# hand_pdn_v2.net
KiCad netlist of a schematic drawn in Altium Designer
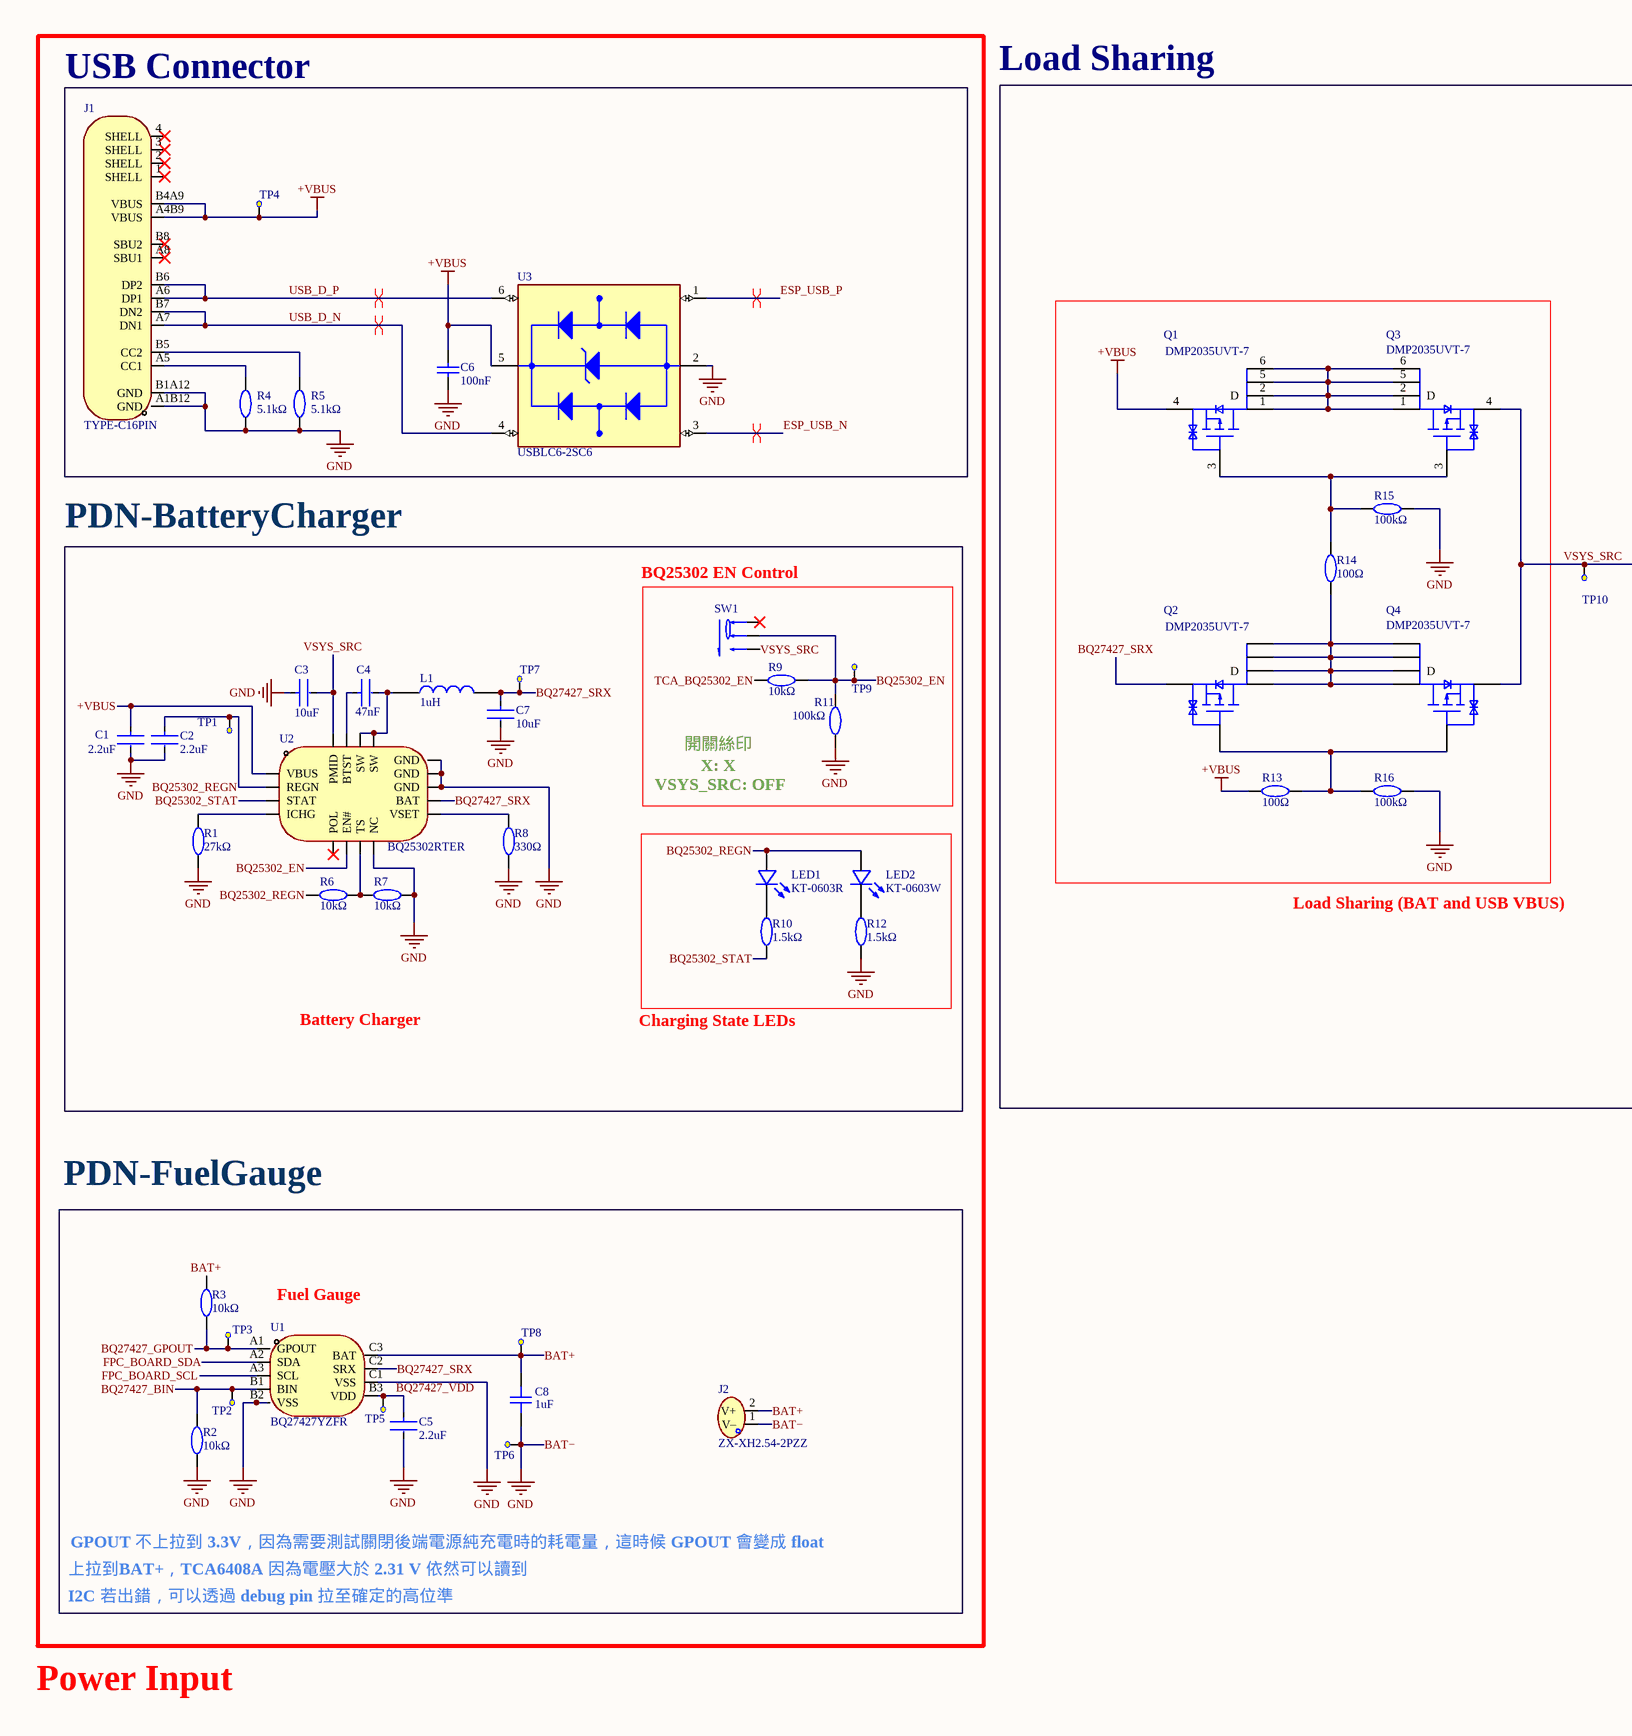
[diagram p0: hand_pdn_v2.SchDoc, left]
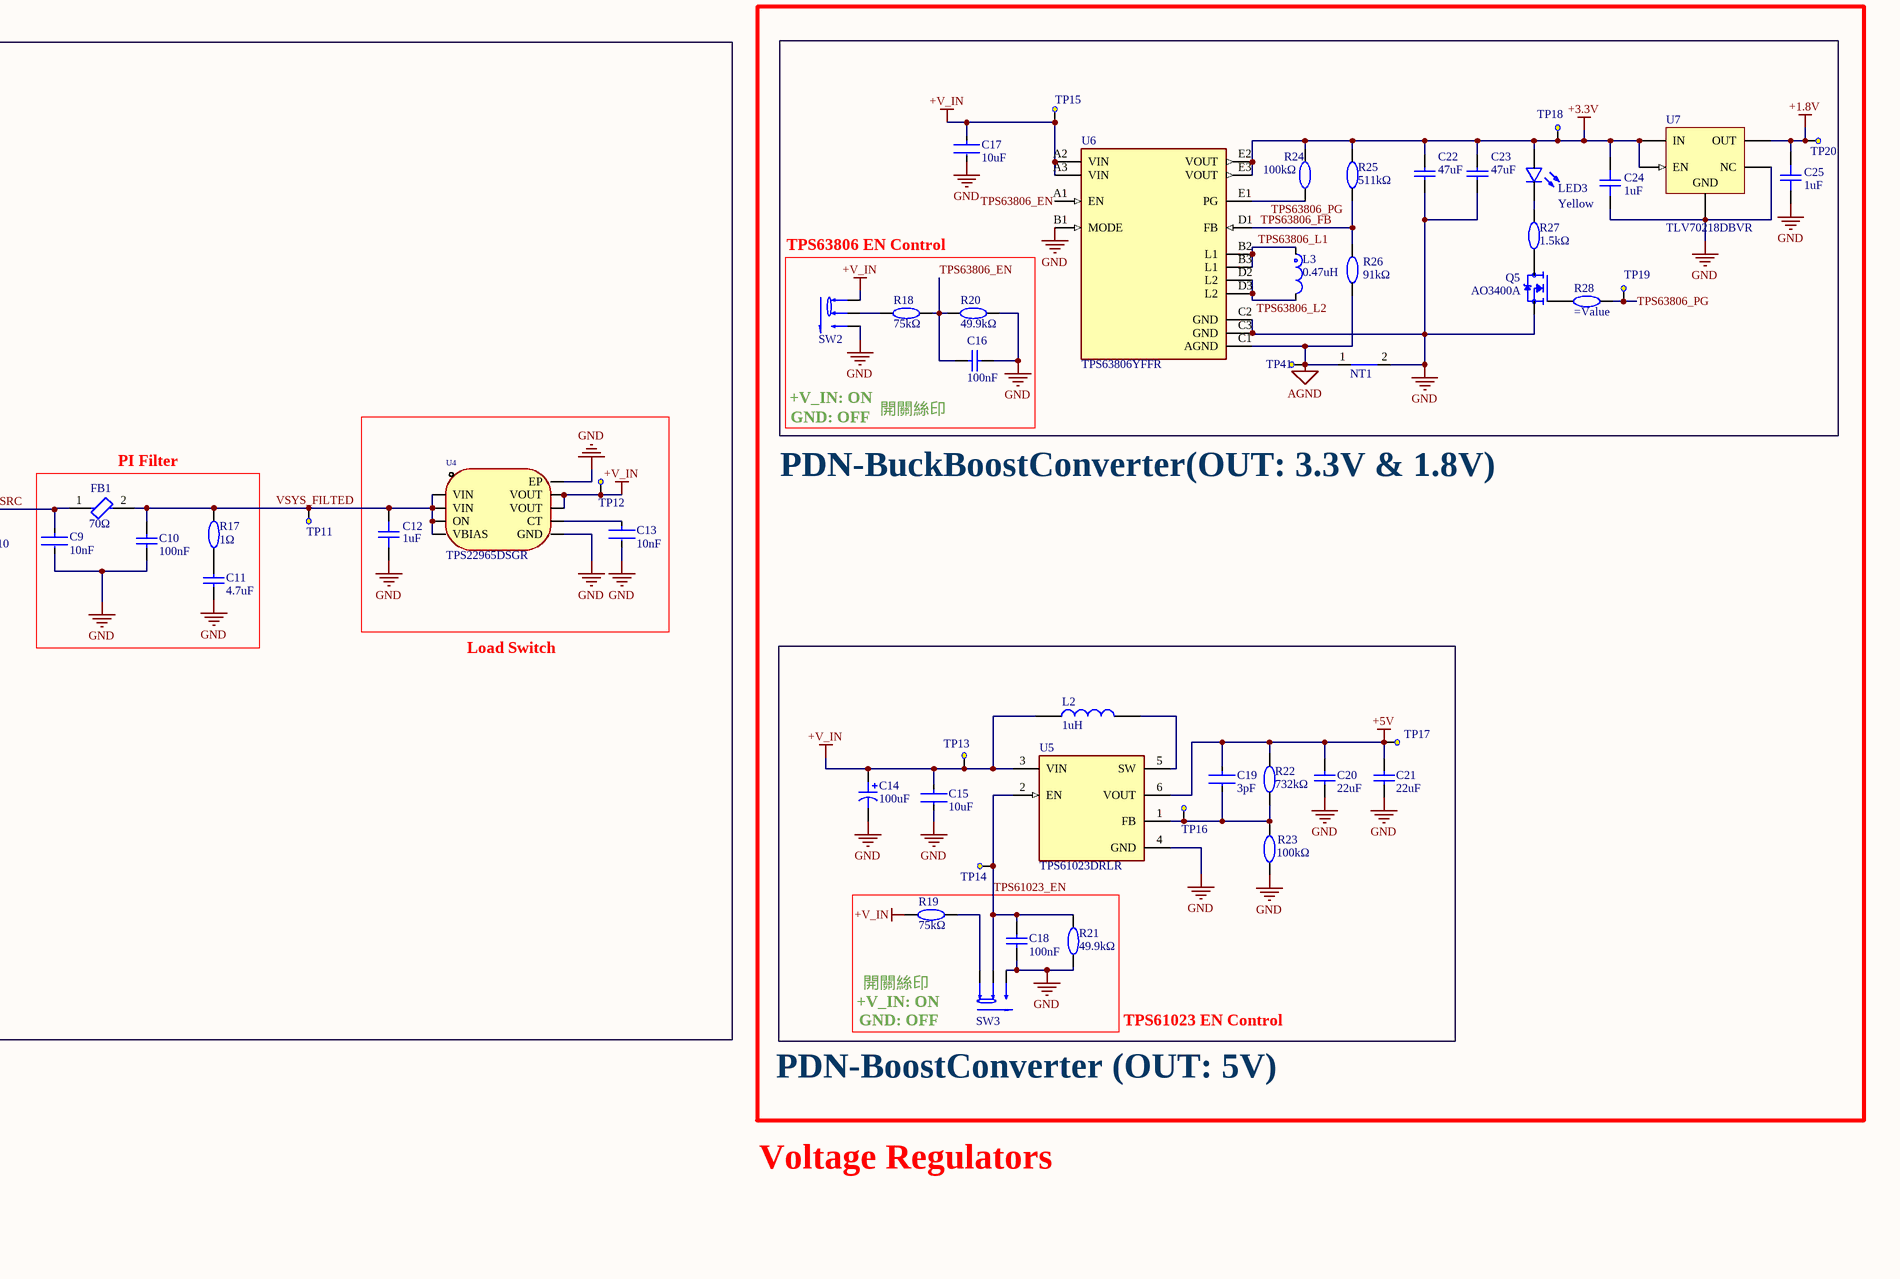
[diagram p1: hand_pdn_v2.SchDoc, right]

(export (version "E")
  (design (tool "Eeschema 10.0.6"))
  (components
    (comp (ref "C1")
      (value "2.2uF")
      (footprint "FP-CL10-IPC_A")
      (description "Cap Ceramic 2.2uF 16V X5R ±10% Pad SMD 0603 +85°C T/R")
      (fields (field (name "TOLERANCE") "10%") (field (name "VOLTAGE") "16V"))
      (libsource (lib "hand_ad_lib") (part "CL10A225KO8NNNC"))
    )
    (comp (ref "C2")
      (value "2.2uF")
      (footprint "FP-CL10-IPC_A")
      (description "Cap Ceramic 2.2uF 16V X5R ±10% Pad SMD 0603 +85°C T/R")
      (fields (field (name "TOLERANCE") "10%") (field (name "VOLTAGE") "16V"))
      (libsource (lib "hand_ad_lib") (part "CL10A225KO8NNNC"))
    )
    (comp (ref "C3")
      (value "10uF")
      (footprint "FP-CL10-IPC_A")
      (description "Cap Ceramic 10uF 25V X5R ±20% Pad SMD 0603 +85°C T/R")
      (fields (field (name "TOLERANCE") "20%"))
      (libsource (lib "hand_ad_lib") (part "CL10A106MA8NRNC"))
    )
    (comp (ref "C4")
      (value "47nF")
      (footprint "FP-CL579-IPC_A")
      (description "Cap Ceramic 47nF 16V X7R ±10% SMD 0402 +125°C Paper T/R")
      (fields (field (name "VOLTAGE") "16V") (field (name "TOLERANCE") "10%"))
      (libsource (lib "hand_ad_lib") (part "CL05B473KO5NNNC"))
    )
    (comp (ref "C5")
      (value "2.2uF")
      (footprint "FP-CL10-IPC_A")
      (description "Cap Ceramic 2.2uF 16V X5R ±10% Pad SMD 0603 +85°C T/R")
      (fields (field (name "TOLERANCE") "10%") (field (name "VOLTAGE") "16V"))
      (libsource (lib "hand_ad_lib") (part "CL10A225KO8NNNC"))
    )
    (comp (ref "C6")
      (value "100nF")
      (footprint "CAPC1050X55X23NL05T13")
      (description "Chip Capacitor, 100 nF, +/- 10%, 16 V, -55 to 125 degC, 0402 (1005 Metric), RoHS, Tape and Reel")
      (fields (field (name "MANUFACTURER") "Samsung Electro-Mechanics"))
      (libsource (lib "hand_ad_lib") (part "CL05B104KO5NNNC"))
    )
    (comp (ref "C7")
      (value "10uF")
      (footprint "FP-CL10-IPC_A")
      (description "Cap Ceramic 10uF 25V X5R ±20% Pad SMD 0603 +85°C T/R")
      (fields (field (name "TOLERANCE") "20%"))
      (libsource (lib "hand_ad_lib") (part "CL10A106MA8NRNC"))
    )
    (comp (ref "C8")
      (value "1uF")
      (footprint "C0402")
      (description "MLCC, 1 uF, 25 V, ± 10%, X5R, 0402 [1005 Metric]")
      (fields
        (field (name "MANUFACTURER") "SAMSUNG(三星)")
        (field (name "MANUFACTURER PART") "CL05A105KA5NQNC")
        (field (name "NAME") "1uF")
      )
      (libsource (lib "hand_ad_lib") (part "CL05A105KA5NQNC"))
    )
    (comp (ref "C9")
      (value "10nF")
      (footprint "FP-CL165-IPC_B")
      (description "Cap Ceramic 10nF 50V X7R ±10% SMD 0402 +125°C Paper T/R")
      (fields (field (name "VOLTAGE") "50V") (field (name "TOLERANCE") "10%"))
      (libsource (lib "hand_ad_lib") (part "CL05B103KB5NNNC"))
    )
    (comp (ref "C10")
      (value "100nF")
      (footprint "CAPC1050X55X23NL05T13")
      (description "Chip Capacitor, 100 nF, +/- 10%, 16 V, -55 to 125 degC, 0402 (1005 Metric), RoHS, Tape and Reel")
      (fields (field (name "MANUFACTURER") "Samsung Electro-Mechanics"))
      (libsource (lib "hand_ad_lib") (part "CL05B104KO5NNNC"))
    )
    (comp (ref "C11")
      (value "4.7uF")
      (footprint "C0603")
      (description "Multilayer Ceramic Capacitor, 4.7 uF, 16 V, ± 10%, X5R, 0603 [1608 Metric]")
      (fields
        (field (name "MANUFACTURER PART") "CL10A475KO8NNNC")
        (field (name "MANUFACTURER") "SAMSUNG(三星)")
        (field (name "NAME") "4.7uF")
      )
      (libsource (lib "hand_ad_lib") (part "CL10A475KO8NNNC"))
    )
    (comp (ref "C12")
      (value "1uF")
      (footprint "C0402")
      (description "MLCC, 1 uF, 25 V, ± 10%, X5R, 0402 [1005 Metric]")
      (fields
        (field (name "MANUFACTURER") "SAMSUNG(三星)")
        (field (name "MANUFACTURER PART") "CL05A105KA5NQNC")
        (field (name "NAME") "1uF")
      )
      (libsource (lib "hand_ad_lib") (part "CL05A105KA5NQNC"))
    )
    (comp (ref "C13")
      (value "10nF")
      (footprint "FP-CL165-IPC_B")
      (description "Cap Ceramic 10nF 50V X7R ±10% SMD 0402 +125°C Paper T/R")
      (fields (field (name "VOLTAGE") "50V") (field (name "TOLERANCE") "10%"))
      (libsource (lib "hand_ad_lib") (part "CL05B103KB5NNNC"))
    )
    (comp (ref "C14")
      (value "100uF")
      (footprint "CAP-SMD_BD6.3-L6.6-W6.6-LS7.2-FD")
      (description "100uF 16V SMD, D6.3xL5.4mm Aluminum Electrolytic Capacitors - SMD ROHS")
      (fields
        (field (name "MANUFACTURER") "KNSCHA(科尼盛)")
        (field (name "MANUFACTURER PART") "RVE100UF16V67RV0046")
        (field (name "NAME") "100uF")
      )
      (libsource (lib "hand_ad_lib") (part "RVE100UF16V67RV0046"))
    )
    (comp (ref "C15")
      (value "10uF")
      (footprint "FP-CL10-IPC_A")
      (description "Cap Ceramic 10uF 25V X5R ±20% Pad SMD 0603 +85°C T/R")
      (fields (field (name "TOLERANCE") "20%"))
      (libsource (lib "hand_ad_lib") (part "CL10A106MA8NRNC"))
    )
    (comp (ref "C16")
      (value "100nF")
      (footprint "CAPC1050X55X23NL05T13")
      (description "Chip Capacitor, 100 nF, +/- 10%, 16 V, -55 to 125 degC, 0402 (1005 Metric), RoHS, Tape and Reel")
      (fields (field (name "MANUFACTURER") "Samsung Electro-Mechanics"))
      (libsource (lib "hand_ad_lib") (part "CL05B104KO5NNNC"))
    )
    (comp (ref "C17")
      (value "10uF")
      (footprint "FP-CL10-IPC_A")
      (description "Cap Ceramic 10uF 25V X5R ±20% Pad SMD 0603 +85°C T/R")
      (fields (field (name "TOLERANCE") "20%"))
      (libsource (lib "hand_ad_lib") (part "CL10A106MA8NRNC"))
    )
    (comp (ref "C18")
      (value "100nF")
      (footprint "CAPC1050X55X23NL05T13")
      (description "Chip Capacitor, 100 nF, +/- 10%, 16 V, -55 to 125 degC, 0402 (1005 Metric), RoHS, Tape and Reel")
      (fields (field (name "MANUFACTURER") "Samsung Electro-Mechanics"))
      (libsource (lib "hand_ad_lib") (part "CL05B104KO5NNNC"))
    )
    (comp (ref "C19")
      (value "3pF")
      (footprint "FP-GJM155-0_05-IPC_C")
      (description "Multi-Layer Ceramic Capacitor 3pF C0G  ±0.05pF 0402 Paper T/R")
      (libsource (lib "hand_ad_lib") (part "GJM1555C1H3R0WB01D"))
    )
    (comp (ref "C20")
      (value "22uF")
      (footprint "CAPC2013X140X45ML15T25")
      (description "Multi-layer Ceramic Capacitor, 22 uF, -55 to 85 degC, 2-Pin SMD (0805), RoHS, Tape and Reel")
      (fields (field (name "MANUFACTURER") "Samsung Electro-Mechanics") (field (name "TOLERANCE") "±20%"))
      (libsource (lib "hand_ad_lib") (part "CL21A226MAQNNNE"))
    )
    (comp (ref "C21")
      (value "22uF")
      (footprint "CAPC2013X140X45ML15T25")
      (description "Multi-layer Ceramic Capacitor, 22 uF, -55 to 85 degC, 2-Pin SMD (0805), RoHS, Tape and Reel")
      (fields (field (name "MANUFACTURER") "Samsung Electro-Mechanics") (field (name "TOLERANCE") "±20%"))
      (libsource (lib "hand_ad_lib") (part "CL21A226MAQNNNE"))
    )
    (comp (ref "C22")
      (value "47uF")
      (footprint "C0805")
      (description "MLCC, 47 uF, 6.3 V, ± 20%, X5R, 0805 [2012 Metric]")
      (fields
        (field (name "MANUFACTURER PART") "CL21A476MQYNNNE")
        (field (name "MANUFACTURER") "SAMSUNG(三星)")
        (field (name "NAME") "47uF")
      )
      (libsource (lib "hand_ad_lib") (part "CL21A476MQYNNNE"))
    )
    (comp (ref "C23")
      (value "47uF")
      (footprint "C0805")
      (description "MLCC, 47 uF, 6.3 V, ± 20%, X5R, 0805 [2012 Metric]")
      (fields
        (field (name "MANUFACTURER PART") "CL21A476MQYNNNE")
        (field (name "MANUFACTURER") "SAMSUNG(三星)")
        (field (name "NAME") "47uF")
      )
      (libsource (lib "hand_ad_lib") (part "CL21A476MQYNNNE"))
    )
    (comp (ref "C24")
      (value "1uF")
      (footprint "C0402")
      (description "MLCC, 1 uF, 25 V, ± 10%, X5R, 0402 [1005 Metric]")
      (fields
        (field (name "MANUFACTURER") "SAMSUNG(三星)")
        (field (name "MANUFACTURER PART") "CL05A105KA5NQNC")
        (field (name "NAME") "1uF")
      )
      (libsource (lib "hand_ad_lib") (part "CL05A105KA5NQNC"))
    )
    (comp (ref "C25")
      (value "1uF")
      (footprint "C0402")
      (description "MLCC, 1 uF, 25 V, ± 10%, X5R, 0402 [1005 Metric]")
      (fields
        (field (name "MANUFACTURER") "SAMSUNG(三星)")
        (field (name "MANUFACTURER PART") "CL05A105KA5NQNC")
        (field (name "NAME") "1uF")
      )
      (libsource (lib "hand_ad_lib") (part "CL05A105KA5NQNC"))
    )
    (comp (ref "FB1")
      (value "70Ω")
      (footprint "FP-BLM18-0_15-t0_5-d1_2-IPC_B")
      (description "Chip Ferrite Bead, 0603, 70Ω @ 100MHz, 25%, 0.02Ω, 4A")
      (libsource (lib "hand_ad_lib") (part "BLM18SG700TZ1D"))
    )
    (comp (ref "J1")
      (value "TYPE-C16PIN")
      (footprint "USB-C-SMD_TYPE-C16PIN")
      (description "USB Type-C 16 pins connector")
      (fields (field (name "MANUFACTURER") "SHOU HAN(首韩)") (field (name "NAME") "TYPE-C16PIN"))
      (libsource (lib "hand_ad_lib") (part "TYPE-C16PIN"))
    )
    (comp (ref "J2")
      (value "ZX-XH2.54-2PZZ")
      (footprint "CONN-TH_2P-P2.50_HX25003-2A")
      (description "XH-2.54 2 Pin, through hole")
      (fields (field (name "MANUFACTURER") "Megastar(兆星)") (field (name "NAME") "ZX-XH2.54-2PZZ"))
      (libsource (lib "hand_ad_lib") (part "ZX-XH2.54-2PZZ"))
    )
    (comp (ref "L1")
      (value "1uH")
      (footprint "XEL4030101MED")
      (description "Power inductor, shielded, 20% tol, SMT, RoHS, halogen-free")
      (fields
        (field (name "MANUFACTURER_PART_NUMBER") "XEL4030-102MEC")
        (field (name "MOUSER PART NUMBER") "994-XEL4030-102MEC")
      )
      (libsource (lib "hand_ad_lib") (part "XEL4030-102MEC"))
    )
    (comp (ref "L2")
      (value "1uH")
      (footprint "XEL4030101MED")
      (description "Power inductor, shielded, 20% tol, SMT, RoHS, halogen-free")
      (fields
        (field (name "MANUFACTURER_PART_NUMBER") "XEL4030-102MEC")
        (field (name "MOUSER PART NUMBER") "994-XEL4030-102MEC")
      )
      (libsource (lib "hand_ad_lib") (part "XEL4030-102MEC"))
    )
    (comp (ref "L3")
      (value "0.47uH")
      (footprint "FP-XFL4015-MFG")
      (description "Shielded Power Fixed Inductor 0.47µH 11.2A 8.36mOhm AECQ2, SFR 89MHz")
      (fields (field (name "TOLERANCE") "20%"))
      (libsource (lib "hand_ad_lib") (part "XFL4015-471MEC"))
    )
    (comp (ref "LED1")
      (value "KT-0603R")
      (footprint "LED0603-RD")
      (description "LED, Red 0603")
      (fields (field (name "MANUFACTURER") "KENTO") (field (name "NAME") "KT-0603R"))
      (libsource (lib "hand_ad_lib") (part "KT-0603R"))
    )
    (comp (ref "LED2")
      (value "KT-0603W")
      (footprint "LED0603-R-RD_WHITE")
      (description "LED, White 0603")
      (fields (field (name "MANUFACTURER") "KENTO") (field (name "NAME") "KT-0603W"))
      (libsource (lib "hand_ad_lib") (part "KT-0603W"))
    )
    (comp (ref "LED3")
      (value "19-213/Y2C-CQ2R2L/3T(CY)")
      (footprint "LED0603-RD-YELLOW")
      (description "LED, Yellow 0603")
      (fields (field (name "MANUFACTURER") "EVERLIGHT(亿光)") (field (name "NAME") "Yellow"))
      (libsource (lib "hand_ad_lib") (part "19-213/Y2C-CQ2R2L/3T(CY)"))
    )
    (comp (ref "NT1") (value "NT") (footprint "NT") (libsource (lib "hand_ad_lib") (part "NetTie_SMD")))
    (comp (ref "Q1")
      (value "DMP2035UVT-7")
      (footprint "SOT-26_L3.0-W1.6-P0.95-LS2.8-BL")
      (description "P-Channel 20 V 35 mOhm Surface Mount Enhancement Mode Mosfet - TSOT26-6")
      (fields (field (name "MANUFACTURER") "DIODES(美台)") (field (name "NAME") "DMP2035UVT-7"))
      (libsource (lib "hand_ad_lib") (part "DMP2035UVT-7"))
    )
    (comp (ref "Q2")
      (value "DMP2035UVT-7")
      (footprint "SOT-26_L3.0-W1.6-P0.95-LS2.8-BL")
      (description "P-Channel 20 V 35 mOhm Surface Mount Enhancement Mode Mosfet - TSOT26-6")
      (fields (field (name "MANUFACTURER") "DIODES(美台)") (field (name "NAME") "DMP2035UVT-7"))
      (libsource (lib "") (part "DMP2035UVT-7_1"))
    )
    (comp (ref "Q3")
      (value "DMP2035UVT-7")
      (footprint "SOT-26_L3.0-W1.6-P0.95-LS2.8-BL")
      (description "P-Channel 20 V 35 mOhm Surface Mount Enhancement Mode Mosfet - TSOT26-6")
      (fields (field (name "MANUFACTURER") "DIODES(美台)") (field (name "NAME") "DMP2035UVT-7"))
      (libsource (lib "hand_ad_lib") (part "DMP2035UVT-7"))
    )
    (comp (ref "Q4")
      (value "DMP2035UVT-7")
      (footprint "SOT-26_L3.0-W1.6-P0.95-LS2.8-BL")
      (description "P-Channel 20 V 35 mOhm Surface Mount Enhancement Mode Mosfet - TSOT26-6")
      (fields (field (name "MANUFACTURER") "DIODES(美台)") (field (name "NAME") "DMP2035UVT-7"))
      (libsource (lib "") (part "DMP2035UVT-7_1"))
    )
    (comp (ref "Q5")
      (value "AO3400A")
      (footprint "FP-SOT23-IPC_A")
      (description "MOSFET N-CH 30V 5.7A SOT23, C20917, Vth from 0.65 - 1.45 V")
      (libsource (lib "hand_ad_lib") (part "AO3400A"))
    )
    (comp (ref "R1")
      (value "27kΩ")
      (footprint "R0603")
      (description "Resistor, Res Thick Film 0603 27K Ohm 1% 0.1W ±100ppm/°C Pad SMD T/R")
      (fields
        (field (name "MANUFACTURER") "UNI-ROYAL(厚声)")
        (field (name "MANUFACTURER PART") "0603WAF2702T5E")
        (field (name "NAME") "27kΩ")
      )
      (libsource (lib "hand_ad_lib") (part "0603WAF2702T5E"))
    )
    (comp (ref "R2")
      (value "10kΩ")
      (footprint "R0402")
      (description "Resistor, Res Thick Film 0402 10K Ohm 1% 0.063W(1/16W) ±100ppm/°C Pad SMD T/R")
      (fields
        (field (name "MANUFACTURER") "UNI-ROYAL(厚声)")
        (field (name "MANUFACTURER PART") "0402WGF1002TCE")
        (field (name "NAME") "10kΩ")
      )
      (libsource (lib "hand_ad_lib") (part "0402WGF1002TCE"))
    )
    (comp (ref "R3")
      (value "10kΩ")
      (footprint "R0402")
      (description "Resistor, Res Thick Film 0402 10K Ohm 1% 0.063W(1/16W) ±100ppm/°C Pad SMD T/R")
      (fields
        (field (name "MANUFACTURER") "UNI-ROYAL(厚声)")
        (field (name "MANUFACTURER PART") "0402WGF1002TCE")
        (field (name "NAME") "10kΩ")
      )
      (libsource (lib "hand_ad_lib") (part "0402WGF1002TCE"))
    )
    (comp (ref "R4")
      (value "5.1kΩ")
      (footprint "R0402")
      (fields
        (field (name "MANUFACTURER") "UNI-ROYAL(厚声)")
        (field (name "MANUFACTURER PART") "0402WGF5101TCE")
        (field (name "TOLERANCE") "±1%")
        (field (name "NAME") "5.1kΩ")
      )
      (libsource (lib "hand_ad_lib") (part "0402WGF5101TCE"))
    )
    (comp (ref "R5")
      (value "5.1kΩ")
      (footprint "R0402")
      (fields
        (field (name "MANUFACTURER") "UNI-ROYAL(厚声)")
        (field (name "MANUFACTURER PART") "0402WGF5101TCE")
        (field (name "TOLERANCE") "±1%")
        (field (name "NAME") "5.1kΩ")
      )
      (libsource (lib "hand_ad_lib") (part "0402WGF5101TCE"))
    )
    (comp (ref "R6")
      (value "10kΩ")
      (footprint "R0402")
      (description "Resistor, Res Thick Film 0402 10K Ohm 1% 0.063W(1/16W) ±100ppm/°C Pad SMD T/R")
      (fields
        (field (name "MANUFACTURER") "UNI-ROYAL(厚声)")
        (field (name "MANUFACTURER PART") "0402WGF1002TCE")
        (field (name "NAME") "10kΩ")
      )
      (libsource (lib "hand_ad_lib") (part "0402WGF1002TCE"))
    )
    (comp (ref "R7")
      (value "10kΩ")
      (footprint "R0402")
      (description "Resistor, Res Thick Film 0402 10K Ohm 1% 0.063W(1/16W) ±100ppm/°C Pad SMD T/R")
      (fields
        (field (name "MANUFACTURER") "UNI-ROYAL(厚声)")
        (field (name "MANUFACTURER PART") "0402WGF1002TCE")
        (field (name "NAME") "10kΩ")
      )
      (libsource (lib "hand_ad_lib") (part "0402WGF1002TCE"))
    )
    (comp (ref "R8")
      (value "330Ω")
      (footprint "R0402")
      (description "Resistor, Res Thick Film 0402 330 Ohm 1% 0.063W(1/16W) ±100ppm/°C Pad SMD T/R")
      (fields
        (field (name "MANUFACTURER") "UNI-ROYAL(厚声)")
        (field (name "MANUFACTURER PART") "0402WGF3300TCE")
        (field (name "NAME") "330Ω")
      )
      (libsource (lib "hand_ad_lib") (part "0402WGF3300TCE"))
    )
    (comp (ref "R9")
      (value "10kΩ")
      (footprint "R0402")
      (description "Resistor, Res Thick Film 0402 10K Ohm 1% 0.063W(1/16W) ±100ppm/°C Pad SMD T/R")
      (fields
        (field (name "MANUFACTURER") "UNI-ROYAL(厚声)")
        (field (name "MANUFACTURER PART") "0402WGF1002TCE")
        (field (name "NAME") "10kΩ")
      )
      (libsource (lib "hand_ad_lib") (part "0402WGF1002TCE"))
    )
    (comp (ref "R10")
      (value "1.5kΩ")
      (footprint "R0402")
      (description "Resistor, Res Thick Film 0402 1.5K Ohm 1% 0.063W(1/16W) ±100ppm/°C Pad SMD T/R")
      (fields
        (field (name "MANUFACTURER") "UNI-ROYAL(厚声)")
        (field (name "MANUFACTURER PART") "0402WGF1501TCE")
        (field (name "NAME") "1.5kΩ")
      )
      (libsource (lib "hand_ad_lib") (part "0402WGF1501TCE"))
    )
    (comp (ref "R11")
      (value "100kΩ")
      (footprint "R0402")
      (description "Resistor, Res Thick Film 0402 100K Ohm 1% 0.063W(1/16W) ±100ppm/°C Pad SMD T/R")
      (fields
        (field (name "MANUFACTURER") "UNI-ROYAL(厚声)")
        (field (name "MANUFACTURER PART") "0402WGF1003TCE")
        (field (name "NAME") "100kΩ")
      )
      (libsource (lib "hand_ad_lib") (part "0402WGF1003TCE"))
    )
    (comp (ref "R12")
      (value "1.5kΩ")
      (footprint "R0402")
      (description "Resistor, Res Thick Film 0402 1.5K Ohm 1% 0.063W(1/16W) ±100ppm/°C Pad SMD T/R")
      (fields
        (field (name "MANUFACTURER") "UNI-ROYAL(厚声)")
        (field (name "MANUFACTURER PART") "0402WGF1501TCE")
        (field (name "NAME") "1.5kΩ")
      )
      (libsource (lib "hand_ad_lib") (part "0402WGF1501TCE"))
    )
    (comp (ref "R13")
      (value "100Ω")
      (footprint "R0603")
      (description "Resistor, Res Thick Film 0603 100 Ohm 1% 0.1W(1/10W) ±200ppm/°C Pad SMD T/R")
      (fields
        (field (name "MANUFACTURER") "UNI-ROYAL(厚声)")
        (field (name "MANUFACTURER PART") "0603WAF1000T5E")
        (field (name "NAME") "100Ω")
      )
      (libsource (lib "hand_ad_lib") (part "0603WAF1000T5E"))
    )
    (comp (ref "R14")
      (value "100Ω")
      (footprint "R0603")
      (description "Resistor, Res Thick Film 0603 100 Ohm 1% 0.1W(1/10W) ±200ppm/°C Pad SMD T/R")
      (fields
        (field (name "MANUFACTURER") "UNI-ROYAL(厚声)")
        (field (name "MANUFACTURER PART") "0603WAF1000T5E")
        (field (name "NAME") "100Ω")
      )
      (libsource (lib "hand_ad_lib") (part "0603WAF1000T5E"))
    )
    (comp (ref "R15")
      (value "100kΩ")
      (footprint "R0402")
      (description "Resistor, Res Thick Film 0402 100K Ohm 1% 0.063W(1/16W) ±100ppm/°C Pad SMD T/R")
      (fields
        (field (name "MANUFACTURER") "UNI-ROYAL(厚声)")
        (field (name "MANUFACTURER PART") "0402WGF1003TCE")
        (field (name "NAME") "100kΩ")
      )
      (libsource (lib "hand_ad_lib") (part "0402WGF1003TCE"))
    )
    (comp (ref "R16")
      (value "100kΩ")
      (footprint "R0402")
      (description "Resistor, Res Thick Film 0402 100K Ohm 1% 0.063W(1/16W) ±100ppm/°C Pad SMD T/R")
      (fields
        (field (name "MANUFACTURER") "UNI-ROYAL(厚声)")
        (field (name "MANUFACTURER PART") "0402WGF1003TCE")
        (field (name "NAME") "100kΩ")
      )
      (libsource (lib "hand_ad_lib") (part "0402WGF1003TCE"))
    )
    (comp (ref "R17")
      (value "1Ω")
      (footprint "R0805")
      (fields
        (field (name "MANUFACTURER") "UNI-ROYAL(厚声)")
        (field (name "MANUFACTURER PART") "0805W8F100KT5E")
        (field (name "TOLERANCE") "±1%")
        (field (name "NAME") "1Ω")
      )
      (libsource (lib "hand_ad_lib") (part "0805W8F100KT5E"))
    )
    (comp (ref "R18")
      (value "75kΩ")
      (footprint "R0603")
      (description "Resistor, Res Thick Film 0603 75k Ohm 1% 0.1W(1/10W) ±100ppm/°C Pad SMD T/R")
      (fields
        (field (name "MANUFACTURER") "UNI-ROYAL(厚声)")
        (field (name "MANUFACTURER PART") "0603WAF7502T5E")
        (field (name "NAME") "75kΩ")
      )
      (libsource (lib "hand_ad_lib") (part "0603WAF7502T5E"))
    )
    (comp (ref "R19")
      (value "75kΩ")
      (footprint "R0603")
      (description "Resistor, Res Thick Film 0603 75k Ohm 1% 0.1W(1/10W) ±100ppm/°C Pad SMD T/R")
      (fields
        (field (name "MANUFACTURER") "UNI-ROYAL(厚声)")
        (field (name "MANUFACTURER PART") "0603WAF7502T5E")
        (field (name "NAME") "75kΩ")
      )
      (libsource (lib "hand_ad_lib") (part "0603WAF7502T5E"))
    )
    (comp (ref "R20")
      (value "49.9kΩ")
      (footprint "R0603")
      (description "Resistor, Res Thick Film 0603 49.9k Ohm 1% 0.1W(1/10W) ±100ppm/°C Pad SMD T/R")
      (fields
        (field (name "MANUFACTURER") "UNI-ROYAL(厚声)")
        (field (name "MANUFACTURER PART") "0603WAF4992T5E")
        (field (name "NAME") "49.9kΩ")
      )
      (libsource (lib "hand_ad_lib") (part "0603WAF4992T5E"))
    )
    (comp (ref "R21")
      (value "49.9kΩ")
      (footprint "R0603")
      (description "Resistor, Res Thick Film 0603 49.9k Ohm 1% 0.1W(1/10W) ±100ppm/°C Pad SMD T/R")
      (fields
        (field (name "MANUFACTURER") "UNI-ROYAL(厚声)")
        (field (name "MANUFACTURER PART") "0603WAF4992T5E")
        (field (name "NAME") "49.9kΩ")
      )
      (libsource (lib "hand_ad_lib") (part "0603WAF4992T5E"))
    )
    (comp (ref "R22")
      (value "732kΩ")
      (footprint "R0603")
      (description "RES SMD 732K OHM 1% 1/10W 0603")
      (fields
        (field (name "MANUFACTURER") "YAGEO(国巨)")
        (field (name "MANUFACTURER PART") "RC0603FR-07732KL")
        (field (name "NAME") "732kΩ")
      )
      (libsource (lib "hand_ad_lib") (part "RC0603FR-07732KL"))
    )
    (comp (ref "R23")
      (value "100kΩ")
      (footprint "R0402")
      (description "Resistor, Res Thick Film 0402 100K Ohm 1% 0.063W(1/16W) ±100ppm/°C Pad SMD T/R")
      (fields
        (field (name "MANUFACTURER") "UNI-ROYAL(厚声)")
        (field (name "MANUFACTURER PART") "0402WGF1003TCE")
        (field (name "NAME") "100kΩ")
      )
      (libsource (lib "hand_ad_lib") (part "0402WGF1003TCE"))
    )
    (comp (ref "R24")
      (value "100kΩ")
      (footprint "R0402")
      (description "Resistor, Res Thick Film 0402 100K Ohm 1% 0.063W(1/16W) ±100ppm/°C Pad SMD T/R")
      (fields
        (field (name "MANUFACTURER") "UNI-ROYAL(厚声)")
        (field (name "MANUFACTURER PART") "0402WGF1003TCE")
        (field (name "NAME") "100kΩ")
      )
      (libsource (lib "hand_ad_lib") (part "0402WGF1003TCE"))
    )
    (comp (ref "R25")
      (value "511kΩ")
      (footprint "R0603")
      (description "Resistor, Res Thick Film 0402 511k Ohm 1% 0.1W(1/10W) ±100ppm/°C Pad SMD T/R")
      (fields
        (field (name "MANUFACTURER") "YAGEO(国巨)")
        (field (name "MANUFACTURER PART") "RC0603FR-07511KL")
        (field (name "NAME") "511kΩ")
      )
      (libsource (lib "hand_ad_lib") (part "RC0603FR-07511KL"))
    )
    (comp (ref "R26")
      (value "91kΩ")
      (footprint "R0402")
      (description "SMD Chip Resistor, 91 kOhm, ± 1%, 63 mW, 0402 [1005 Metric], Thick Film, General Purpose")
      (fields
        (field (name "MANUFACTURER") "YAGEO(国巨)")
        (field (name "MANUFACTURER PART") "AC0402FR-0791KL")
        (field (name "NAME") "91kΩ")
      )
      (libsource (lib "hand_ad_lib") (part "AC0402FR-0791KL"))
    )
    (comp (ref "R27")
      (value "1.5kΩ")
      (footprint "R0402")
      (description "Resistor, Res Thick Film 0402 1.5K Ohm 1% 0.063W(1/16W) ±100ppm/°C Pad SMD T/R")
      (fields
        (field (name "MANUFACTURER") "UNI-ROYAL(厚声)")
        (field (name "MANUFACTURER PART") "0402WGF1501TCE")
        (field (name "NAME") "1.5kΩ")
      )
      (libsource (lib "hand_ad_lib") (part "0402WGF1501TCE"))
    )
    (comp (ref "R28")
      (value "~")
      (footprint "R0402")
      (description "Resistor, Res Thick Film 0402 1K Ohm 1% 0.063W(1/16W) ±100ppm/°C Pad SMD T/R")
      (fields
        (field (name "MANUFACTURER") "UNI-ROYAL(厚声)")
        (field (name "MANUFACTURER PART") "0402WGF1001TCE")
      )
      (libsource (lib "hand_ad_lib") (part "0402WGF1001TCE"))
    )
    (comp (ref "SW1")
      (value "MST-22D18G2 3J")
      (footprint "SW-SMD_SHOUHAN_MST-22D18G23J_C2875122")
      (fields (field (name "MANUFACTURER") "SHOU HAN(首韩)"))
      (libsource (lib "hand_ad_lib") (part "MST-22D18G2 3J"))
    )
    (comp (ref "SW2")
      (value "MST-22D18G2 3J")
      (footprint "SW-SMD_SHOUHAN_MST-22D18G23J_C2875122")
      (fields (field (name "MANUFACTURER") "SHOU HAN(首韩)"))
      (libsource (lib "hand_ad_lib") (part "MST-22D18G2 3J"))
    )
    (comp (ref "SW3")
      (value "MST-22D18G2 3J")
      (footprint "SW-SMD_SHOUHAN_MST-22D18G23J_C2875122")
      (fields (field (name "MANUFACTURER") "SHOU HAN(首韩)"))
      (libsource (lib "hand_ad_lib") (part "MST-22D18G2 3J"))
    )
    (comp (ref "TP1")
      (value "Test point")
      (footprint "Test_Point")
      (libsource (lib "hand_ad_lib") (part "Test_Point"))
    )
    (comp (ref "TP2")
      (value "Test point")
      (footprint "Test_Point")
      (libsource (lib "hand_ad_lib") (part "Test_Point"))
    )
    (comp (ref "TP3")
      (value "Test point")
      (footprint "Test_Point")
      (libsource (lib "hand_ad_lib") (part "Test_Point"))
    )
    (comp (ref "TP4")
      (value "Test point")
      (footprint "Test_Point")
      (libsource (lib "hand_ad_lib") (part "Test_Point"))
    )
    (comp (ref "TP5")
      (value "Test point")
      (footprint "Test_Point")
      (libsource (lib "hand_ad_lib") (part "Test_Point"))
    )
    (comp (ref "TP6")
      (value "Test point")
      (footprint "Test_Point")
      (libsource (lib "hand_ad_lib") (part "Test_Point"))
    )
    (comp (ref "TP7")
      (value "Test point")
      (footprint "Test_Point")
      (libsource (lib "hand_ad_lib") (part "Test_Point"))
    )
    (comp (ref "TP8")
      (value "Test point")
      (footprint "Test_Point")
      (libsource (lib "hand_ad_lib") (part "Test_Point"))
    )
    (comp (ref "TP9")
      (value "Test point")
      (footprint "Test_Point")
      (libsource (lib "hand_ad_lib") (part "Test_Point"))
    )
    (comp (ref "TP10")
      (value "Test point")
      (footprint "Test_Point")
      (libsource (lib "hand_ad_lib") (part "Test_Point"))
    )
    (comp (ref "TP11")
      (value "Test point")
      (footprint "Test_Point")
      (libsource (lib "hand_ad_lib") (part "Test_Point"))
    )
    (comp (ref "TP12")
      (value "Test point")
      (footprint "Test_Point")
      (libsource (lib "hand_ad_lib") (part "Test_Point"))
    )
    (comp (ref "TP13")
      (value "Test point")
      (footprint "Test_Point")
      (libsource (lib "hand_ad_lib") (part "Test_Point"))
    )
    (comp (ref "TP14")
      (value "Test point")
      (footprint "Test_Point")
      (libsource (lib "hand_ad_lib") (part "Test_Point"))
    )
    (comp (ref "TP15")
      (value "Test point")
      (footprint "Test_Point")
      (libsource (lib "hand_ad_lib") (part "Test_Point"))
    )
    (comp (ref "TP16")
      (value "Test point")
      (footprint "Test_Point")
      (libsource (lib "hand_ad_lib") (part "Test_Point"))
    )
    (comp (ref "TP17")
      (value "Test point")
      (footprint "Test_Point")
      (libsource (lib "hand_ad_lib") (part "Test_Point"))
    )
    (comp (ref "TP18")
      (value "Test point")
      (footprint "Test_Point")
      (libsource (lib "hand_ad_lib") (part "Test_Point"))
    )
    (comp (ref "TP19")
      (value "Test point")
      (footprint "Test_Point")
      (libsource (lib "hand_ad_lib") (part "Test_Point"))
    )
    (comp (ref "TP20")
      (value "Test point")
      (footprint "Test_Point")
      (libsource (lib "hand_ad_lib") (part "Test_Point"))
    )
    (comp (ref "TP41")
      (value "Test point")
      (footprint "Test_Point")
      (libsource (lib "hand_ad_lib") (part "Test_Point"))
    )
    (comp (ref "U1")
      (value "BQ27427YZFR")
      (footprint "DSBGA-9_L1.6-W1.6-R3-C3-P0.50-TL")
      (fields (field (name "MANUFACTURER") "TI(德州仪器)") (field (name "NAME") "BQ27427YZFR"))
      (libsource (lib "hand_ad_lib") (part "BQ27427YZFR"))
    )
    (comp (ref "U2")
      (value "BQ25302RTER")
      (footprint "WQFN-16_L3.0-W3.0-P0.50-BL-EP1.7")
      (description "Standalone single cell 2.0-A buck battery charger 16-WQFN -40 to 85")
      (fields (field (name "MANUFACTURER") "TI(德州仪器)") (field (name "NAME") "BQ25302RTER"))
      (libsource (lib "hand_ad_lib") (part "BQ25302RTER"))
    )
    (comp (ref "U3")
      (value "USBLC6-2SC6")
      (footprint "SOT95P280X145-6N")
      (description "17V Clamp 5A (8/20Âµs) Ipp Tvs Diode Surface Mount SOT-23-6")
      (fields (field (name "MF") "STMicroelectronics"))
      (libsource (lib "hand_ad_lib") (part "USBLC6-2SC6"))
    )
    (comp (ref "U4")
      (value "TPS22965DSGR")
      (footprint "UDFN-8_L2.0-W2.0-P0.50-TL-EP")
      (description "Tape & Reel (TR) TPS22965 e4 On/Off power distribution switch 2mm 2.5V 2.2ms 6A")
      (fields (field (name "MANUFACTURER") "TI(德州仪器)") (field (name "NAME") "TPS22965DSGR"))
      (libsource (lib "hand_ad_lib") (part "TPS22965DSGR"))
    )
    (comp (ref "U5")
      (value "TPS61023DRLR")
      (footprint "FP-DRL0006A-MFG")
      (description "3.7-A boost converter with 0.5-V ultra-low input voltage 6-SOT-5X3 -40 to 125")
      (libsource (lib "hand_ad_lib") (part "TPS61023DRLR"))
    )
    (comp (ref "U6")
      (value "TPS63806YFFR")
      (footprint "FP-YFF0015-MFG")
      (description "Low IQ Buck-Boost Converter with Small Solution Size 2A 1.3V to 5.5V 15-Pin DSBGA")
      (libsource (lib "hand_ad_lib") (part "TPS63806YFFR"))
    )
    (comp (ref "U7")
      (value "TLV70218DBVR")
      (footprint "DBV0005A_M")
      (description "300-mA, high-PSRR, low-IQ, low-dropout voltage regulator with enable 5-SOT-23 -40 to 125")
      (libsource (lib "hand_ad_lib") (part "TLV70218DBVR"))
    )
  )
  (nets
    (net (code "1") (name "+1.8V") (class "Default")
      (node (ref "C25") (pin "2") (pinfunction "2_2") (pintype "passive"))
      (node (ref "TP20") (pin "TP?") (pinfunction "Test_point_TP?") (pintype "passive"))
      (node (ref "U7") (pin "5") (pinfunction "OUT_5") (pintype "power_in"))
    )
    (net (code "2") (name "+3.3V") (class "Default")
      (node (ref "C22") (pin "2") (pinfunction "2_2") (pintype "passive"))
      (node (ref "C23") (pin "2") (pinfunction "2_2") (pintype "passive"))
      (node (ref "C24") (pin "2") (pinfunction "2_2") (pintype "passive"))
      (node (ref "LED3") (pin "2") (pinfunction "A_2") (pintype "passive"))
      (node (ref "R24") (pin "2") (pinfunction "2_2") (pintype "passive"))
      (node (ref "R25") (pin "2") (pinfunction "2_2") (pintype "passive"))
      (node (ref "TP18") (pin "TP?") (pinfunction "Test_point_TP?") (pintype "passive"))
      (node (ref "U6") (pin "E2") (pinfunction "VOUT_E2") (pintype "output"))
      (node (ref "U6") (pin "E3") (pinfunction "VOUT_E3") (pintype "output"))
      (node (ref "U7") (pin "1") (pinfunction "IN_1") (pintype "power_in"))
      (node (ref "U7") (pin "3") (pinfunction "EN_3") (pintype "input"))
    )
    (net (code "3") (name "+5V") (class "Default")
      (node (ref "C19") (pin "1") (pinfunction "1_1") (pintype "passive"))
      (node (ref "C20") (pin "2") (pinfunction "2_2") (pintype "passive"))
      (node (ref "C21") (pin "2") (pinfunction "2_2") (pintype "passive"))
      (node (ref "R22") (pin "2") (pinfunction "2_2") (pintype "passive"))
      (node (ref "TP17") (pin "TP?") (pinfunction "Test_point_TP?") (pintype "passive"))
      (node (ref "U5") (pin "6") (pinfunction "VOUT_6") (pintype "power_in"))
    )
    (net (code "4") (name "+VBUS") (class "Default")
      (node (ref "C1") (pin "1") (pinfunction "1_1") (pintype "passive"))
      (node (ref "C6") (pin "2") (pinfunction "2_2") (pintype "passive"))
      (node (ref "J1") (pin "A4B9") (pinfunction "VBUS_A4B9") (pintype "passive"))
      (node (ref "J1") (pin "B4A9") (pinfunction "VBUS_B4A9") (pintype "passive"))
      (node (ref "Q1") (pin "4") (pinfunction "S_4") (pintype "passive"))
      (node (ref "R13") (pin "2") (pinfunction "2_2") (pintype "passive"))
      (node (ref "TP4") (pin "TP?") (pinfunction "Test_point_TP?") (pintype "passive"))
      (node (ref "U2") (pin "1") (pinfunction "VBUS_1") (pintype "passive"))
      (node (ref "U3") (pin "5") (pinfunction "VBUS_5") (pintype "power_in"))
    )
    (net (code "5") (name "+V_IN") (class "Default")
      (node (ref "C14") (pin "1") (pinfunction "1_1") (pintype "passive"))
      (node (ref "C15") (pin "1") (pinfunction "1_1") (pintype "passive"))
      (node (ref "C17") (pin "1") (pinfunction "1_1") (pintype "passive"))
      (node (ref "L2") (pin "1") (pinfunction "1_1") (pintype "passive"))
      (node (ref "R19") (pin "1") (pinfunction "1_1") (pintype "passive"))
      (node (ref "SW2") (pin "1") (pinfunction "1_1") (pintype "passive"))
      (node (ref "TP12") (pin "TP?") (pinfunction "Test_point_TP?") (pintype "passive"))
      (node (ref "TP13") (pin "TP?") (pinfunction "Test_point_TP?") (pintype "passive"))
      (node (ref "TP15") (pin "TP?") (pinfunction "Test_point_TP?") (pintype "passive"))
      (node (ref "U4") (pin "7") (pinfunction "VOUT_7") (pintype "passive"))
      (node (ref "U4") (pin "8") (pinfunction "VOUT_8") (pintype "passive"))
      (node (ref "U5") (pin "3") (pinfunction "VIN_3") (pintype "power_in"))
      (node (ref "U6") (pin "A2") (pinfunction "VIN_A2") (pintype "power_in"))
      (node (ref "U6") (pin "A3") (pinfunction "VIN_A3") (pintype "power_in"))
    )
    (net (code "6") (name "/BAT+") (class "Default")
      (node (ref "C8") (pin "2") (pinfunction "2_2") (pintype "passive"))
      (node (ref "J2") (pin "2") (pinfunction "V+_2") (pintype "passive"))
      (node (ref "R3") (pin "2") (pinfunction "2_2") (pintype "passive"))
      (node (ref "TP8") (pin "TP?") (pinfunction "Test_point_TP?") (pintype "passive"))
      (node (ref "U1") (pin "C3") (pinfunction "BAT_C3") (pintype "passive"))
    )
    (net (code "7") (name "/BQ25302_EN") (class "Default")
      (node (ref "R11") (pin "2") (pinfunction "2_2") (pintype "passive"))
      (node (ref "R9") (pin "1") (pinfunction "1_1") (pintype "passive"))
      (node (ref "SW1") (pin "2") (pinfunction "2_2") (pintype "passive"))
      (node (ref "TP9") (pin "TP?") (pinfunction "Test_point_TP?") (pintype "passive"))
      (node (ref "U2") (pin "6") (pinfunction "EN#_6") (pintype "passive"))
    )
    (net (code "8") (name "/BQ25302_REGN") (class "Default")
      (node (ref "C2") (pin "1") (pinfunction "1_1") (pintype "passive"))
      (node (ref "LED1") (pin "2") (pinfunction "A_2") (pintype "passive"))
      (node (ref "LED2") (pin "1") (pinfunction "A_1") (pintype "passive"))
      (node (ref "R6") (pin "1") (pinfunction "1_1") (pintype "passive"))
      (node (ref "TP1") (pin "TP?") (pinfunction "Test_point_TP?") (pintype "passive"))
      (node (ref "U2") (pin "2") (pinfunction "REGN_2") (pintype "passive"))
    )
    (net (code "9") (name "/BQ25302_STAT") (class "Default")
      (node (ref "R10") (pin "1") (pinfunction "1_1") (pintype "passive"))
      (node (ref "U2") (pin "3") (pinfunction "STAT_3") (pintype "passive"))
    )
    (net (code "10") (name "/BQ27427_BIN") (class "Default")
      (node (ref "R2") (pin "2") (pinfunction "2_2") (pintype "passive"))
      (node (ref "TP2") (pin "TP?") (pinfunction "Test_point_TP?") (pintype "passive"))
      (node (ref "U1") (pin "B1") (pinfunction "BIN_B1") (pintype "passive"))
    )
    (net (code "11") (name "/BQ27427_GPOUT") (class "Default")
      (node (ref "R3") (pin "1") (pinfunction "1_1") (pintype "passive"))
      (node (ref "TP3") (pin "TP?") (pinfunction "Test_point_TP?") (pintype "passive"))
      (node (ref "U1") (pin "A1") (pinfunction "GPOUT_A1") (pintype "passive"))
    )
    (net (code "12") (name "/BQ27427_SRX") (class "Default")
      (node (ref "C7") (pin "1") (pinfunction "1_1") (pintype "passive"))
      (node (ref "L1") (pin "2") (pinfunction "2_2") (pintype "passive"))
      (node (ref "Q2") (pin "4") (pinfunction "S_4") (pintype "passive"))
      (node (ref "TP7") (pin "TP?") (pinfunction "Test_point_TP?") (pintype "passive"))
      (node (ref "U1") (pin "C2") (pinfunction "SRX_C2") (pintype "passive"))
      (node (ref "U2") (pin "10") (pinfunction "BAT_10") (pintype "passive"))
    )
    (net (code "13") (name "/BQ27427_VDD") (class "Default")
      (node (ref "C5") (pin "1") (pinfunction "1_1") (pintype "passive"))
      (node (ref "TP5") (pin "TP?") (pinfunction "Test_point_TP?") (pintype "passive"))
      (node (ref "U1") (pin "B3") (pinfunction "VDD_B3") (pintype "passive"))
    )
    (net (code "14") (name "/ESP_USB_N") (class "Default")
      (node (ref "U3") (pin "3") (pinfunction "I/O2_IN_3") (pintype "bidirectional"))
    )
    (net (code "15") (name "/ESP_USB_P") (class "Default")
      (node (ref "U3") (pin "1") (pinfunction "I/O1_IN_1") (pintype "bidirectional"))
    )
    (net (code "16") (name "/FPC_BOARD_SCL") (class "Default")
      (node (ref "U1") (pin "A3") (pinfunction "SCL_A3") (pintype "passive"))
    )
    (net (code "17") (name "/FPC_BOARD_SDA") (class "Default")
      (node (ref "U1") (pin "A2") (pinfunction "SDA_A2") (pintype "passive"))
    )
    (net (code "18") (name "/TCA_BQ25302_EN") (class "Default")
      (node (ref "R9") (pin "2") (pinfunction "2_2") (pintype "passive"))
    )
    (net (code "19") (name "/TPS61023_EN") (class "Default")
      (node (ref "C18") (pin "1") (pinfunction "1_1") (pintype "passive"))
      (node (ref "R21") (pin "2") (pinfunction "2_2") (pintype "passive"))
      (node (ref "SW3") (pin "2") (pinfunction "2_2") (pintype "passive"))
      (node (ref "TP14") (pin "TP?") (pinfunction "Test_point_TP?") (pintype "passive"))
      (node (ref "U5") (pin "2") (pinfunction "EN_2") (pintype "input"))
    )
    (net (code "20") (name "/TPS63806_EN") (class "Default")
      (node (ref "C16") (pin "2") (pinfunction "2_2") (pintype "passive"))
      (node (ref "R18") (pin "2") (pinfunction "2_2") (pintype "passive"))
      (node (ref "R20") (pin "1") (pinfunction "1_1") (pintype "passive"))
      (node (ref "U6") (pin "A1") (pinfunction "EN_A1") (pintype "input"))
    )
    (net (code "21") (name "/TPS63806_FB") (class "Default")
      (node (ref "R25") (pin "1") (pinfunction "1_1") (pintype "passive"))
      (node (ref "R26") (pin "2") (pinfunction "2_2") (pintype "passive"))
      (node (ref "U6") (pin "D1") (pinfunction "FB_D1") (pintype "input"))
    )
    (net (code "22") (name "/TPS63806_L1") (class "Default")
      (node (ref "L3") (pin "1") (pinfunction "1_1") (pintype "passive"))
      (node (ref "U6") (pin "B2") (pinfunction "L1_B2") (pintype "passive"))
      (node (ref "U6") (pin "B3") (pinfunction "L1_B3") (pintype "passive"))
    )
    (net (code "23") (name "/TPS63806_L2") (class "Default")
      (node (ref "L3") (pin "2") (pinfunction "2_2") (pintype "passive"))
      (node (ref "U6") (pin "D2") (pinfunction "L2_D2") (pintype "passive"))
      (node (ref "U6") (pin "D3") (pinfunction "L2_D3") (pintype "passive"))
    )
    (net (code "24") (name "/TPS63806_PG") (class "Default")
      (node (ref "R24") (pin "1") (pinfunction "1_1") (pintype "passive"))
      (node (ref "R28") (pin "2") (pinfunction "2_2") (pintype "passive"))
      (node (ref "TP19") (pin "TP?") (pinfunction "Test_point_TP?") (pintype "passive"))
      (node (ref "U6") (pin "E1") (pinfunction "PG_E1") (pintype "open_collector"))
    )
    (net (code "25") (name "/USB_D_N") (class "Default")
      (node (ref "J1") (pin "A7") (pinfunction "DN1_A7") (pintype "bidirectional"))
      (node (ref "J1") (pin "B7") (pinfunction "DN2_B7") (pintype "bidirectional"))
      (node (ref "U3") (pin "4") (pinfunction "I/O2_OUT_4") (pintype "bidirectional"))
    )
    (net (code "26") (name "/USB_D_P") (class "Default")
      (node (ref "J1") (pin "A6") (pinfunction "DP1_A6") (pintype "bidirectional"))
      (node (ref "J1") (pin "B6") (pinfunction "DP2_B6") (pintype "bidirectional"))
      (node (ref "U3") (pin "6") (pinfunction "I/O1_OUT_6") (pintype "bidirectional"))
    )
    (net (code "27") (name "/VSYS_FILTED") (class "Default")
      (node (ref "C10") (pin "2") (pinfunction "2_2") (pintype "passive"))
      (node (ref "C12") (pin "2") (pinfunction "2_2") (pintype "passive"))
      (node (ref "FB1") (pin "2") (pinfunction "2_2") (pintype "passive"))
      (node (ref "R17") (pin "2") (pinfunction "2_2") (pintype "passive"))
      (node (ref "TP11") (pin "TP?") (pinfunction "Test_point_TP?") (pintype "passive"))
      (node (ref "U4") (pin "1") (pinfunction "VIN_1") (pintype "passive"))
      (node (ref "U4") (pin "2") (pinfunction "VIN_2") (pintype "passive"))
      (node (ref "U4") (pin "3") (pinfunction "ON_3") (pintype "passive"))
      (node (ref "U4") (pin "4") (pinfunction "VBIAS_4") (pintype "passive"))
    )
    (net (code "28") (name "/VSYS_SRC") (class "Default")
      (node (ref "C3") (pin "2") (pinfunction "2_2") (pintype "passive"))
      (node (ref "C9") (pin "1") (pinfunction "1_1") (pintype "passive"))
      (node (ref "FB1") (pin "1") (pinfunction "1_1") (pintype "passive"))
      (node (ref "Q3") (pin "4") (pinfunction "S_4") (pintype "passive"))
      (node (ref "Q4") (pin "4") (pinfunction "S_4") (pintype "passive"))
      (node (ref "SW1") (pin "3") (pinfunction "3_3") (pintype "passive"))
      (node (ref "TP10") (pin "TP?") (pinfunction "Test_point_TP?") (pintype "passive"))
      (node (ref "U2") (pin "16") (pinfunction "PMID_16") (pintype "passive"))
    )
    (net (code "29") (name "AGND") (class "Default")
      (node (ref "NT1") (pin "1") (pinfunction "1_1") (pintype "passive"))
      (node (ref "R26") (pin "1") (pinfunction "1_1") (pintype "passive"))
      (node (ref "TP41") (pin "TP?") (pinfunction "Test_point_TP?") (pintype "passive"))
      (node (ref "U6") (pin "C1") (pinfunction "AGND_C1") (pintype "power_in"))
    )
    (net (code "30") (name "GND") (class "Default")
      (node (ref "C1") (pin "2") (pinfunction "2_2") (pintype "passive"))
      (node (ref "C10") (pin "1") (pinfunction "1_1") (pintype "passive"))
      (node (ref "C11") (pin "1") (pinfunction "1_1") (pintype "passive"))
      (node (ref "C12") (pin "1") (pinfunction "1_1") (pintype "passive"))
      (node (ref "C13") (pin "2") (pinfunction "2_2") (pintype "passive"))
      (node (ref "C14") (pin "2") (pinfunction "2_2") (pintype "passive"))
      (node (ref "C15") (pin "2") (pinfunction "2_2") (pintype "passive"))
      (node (ref "C16") (pin "1") (pinfunction "1_1") (pintype "passive"))
      (node (ref "C17") (pin "2") (pinfunction "2_2") (pintype "passive"))
      (node (ref "C18") (pin "2") (pinfunction "2_2") (pintype "passive"))
      (node (ref "C2") (pin "2") (pinfunction "2_2") (pintype "passive"))
      (node (ref "C20") (pin "1") (pinfunction "1_1") (pintype "passive"))
      (node (ref "C21") (pin "1") (pinfunction "1_1") (pintype "passive"))
      (node (ref "C22") (pin "1") (pinfunction "1_1") (pintype "passive"))
      (node (ref "C23") (pin "1") (pinfunction "1_1") (pintype "passive"))
      (node (ref "C24") (pin "1") (pinfunction "1_1") (pintype "passive"))
      (node (ref "C25") (pin "1") (pinfunction "1_1") (pintype "passive"))
      (node (ref "C3") (pin "1") (pinfunction "1_1") (pintype "passive"))
      (node (ref "C5") (pin "2") (pinfunction "2_2") (pintype "passive"))
      (node (ref "C6") (pin "1") (pinfunction "1_1") (pintype "passive"))
      (node (ref "C7") (pin "2") (pinfunction "2_2") (pintype "passive"))
      (node (ref "C8") (pin "1") (pinfunction "1_1") (pintype "passive"))
      (node (ref "C9") (pin "2") (pinfunction "2_2") (pintype "passive"))
      (node (ref "J1") (pin "A1B12") (pinfunction "GND_A1B12") (pintype "power_in"))
      (node (ref "J1") (pin "B1A12") (pinfunction "GND_B1A12") (pintype "power_in"))
      (node (ref "J2") (pin "1") (pinfunction "V–_1") (pintype "passive"))
      (node (ref "NT1") (pin "2") (pinfunction "2_2") (pintype "passive"))
      (node (ref "Q5") (pin "2") (pinfunction "S_2") (pintype "passive"))
      (node (ref "R1") (pin "1") (pinfunction "1_1") (pintype "passive"))
      (node (ref "R11") (pin "1") (pinfunction "1_1") (pintype "passive"))
      (node (ref "R12") (pin "1") (pinfunction "1_1") (pintype "passive"))
      (node (ref "R15") (pin "1") (pinfunction "1_1") (pintype "passive"))
      (node (ref "R16") (pin "1") (pinfunction "1_1") (pintype "passive"))
      (node (ref "R2") (pin "1") (pinfunction "1_1") (pintype "passive"))
      (node (ref "R20") (pin "2") (pinfunction "2_2") (pintype "passive"))
      (node (ref "R21") (pin "1") (pinfunction "1_1") (pintype "passive"))
      (node (ref "R23") (pin "1") (pinfunction "1_1") (pintype "passive"))
      (node (ref "R4") (pin "1") (pinfunction "1_1") (pintype "passive"))
      (node (ref "R5") (pin "1") (pinfunction "1_1") (pintype "passive"))
      (node (ref "R7") (pin "2") (pinfunction "2_2") (pintype "passive"))
      (node (ref "R8") (pin "1") (pinfunction "1_1") (pintype "passive"))
      (node (ref "SW2") (pin "3") (pinfunction "3_3") (pintype "passive"))
      (node (ref "SW3") (pin "3") (pinfunction "3_3") (pintype "passive"))
      (node (ref "TP6") (pin "TP?") (pinfunction "Test_point_TP?") (pintype "passive"))
      (node (ref "U1") (pin "B2") (pinfunction "VSS_B2") (pintype "passive"))
      (node (ref "U1") (pin "C1") (pinfunction "VSS_C1") (pintype "passive"))
      (node (ref "U2") (pin "11") (pinfunction "GND_11") (pintype "passive"))
      (node (ref "U2") (pin "12") (pinfunction "GND_12") (pintype "passive"))
      (node (ref "U2") (pin "17") (pinfunction "GND_17") (pintype "passive"))
      (node (ref "U2") (pin "8") (pinfunction "NC_8") (pintype "passive"))
      (node (ref "U3") (pin "2") (pinfunction "GND_2") (pintype "power_in"))
      (node (ref "U4") (pin "5") (pinfunction "GND_5") (pintype "passive"))
      (node (ref "U4") (pin "9") (pinfunction "EP_9") (pintype "passive"))
      (node (ref "U5") (pin "4") (pinfunction "GND_4") (pintype "power_in"))
      (node (ref "U6") (pin "B1") (pinfunction "MODE_B1") (pintype "input"))
      (node (ref "U6") (pin "C2") (pinfunction "GND_C2") (pintype "power_in"))
      (node (ref "U6") (pin "C3") (pinfunction "GND_C3") (pintype "power_in"))
      (node (ref "U7") (pin "2") (pinfunction "GND_2") (pintype "power_in"))
      (node (ref "U7") (pin "4") (pinfunction "NC_4") (pintype "passive"))
    )
    (net (code "31") (name "Net-(C4-Pad2)") (class "Default")
      (node (ref "C4") (pin "2") (pinfunction "2_2") (pintype "passive"))
      (node (ref "L1") (pin "1") (pinfunction "1_1") (pintype "passive"))
      (node (ref "U2") (pin "13") (pinfunction "SW_13") (pintype "passive"))
      (node (ref "U2") (pin "14") (pinfunction "SW_14") (pintype "passive"))
    )
    (net (code "32") (name "Net-(C11-Pad2)") (class "Default")
      (node (ref "C11") (pin "2") (pinfunction "2_2") (pintype "passive"))
      (node (ref "R17") (pin "1") (pinfunction "1_1") (pintype "passive"))
    )
    (net (code "33") (name "Net-(J1-CC1)") (class "Default")
      (node (ref "J1") (pin "A5") (pinfunction "CC1_A5") (pintype "passive"))
      (node (ref "R4") (pin "2") (pinfunction "2_2") (pintype "passive"))
    )
    (net (code "34") (name "Net-(J1-CC2)") (class "Default")
      (node (ref "J1") (pin "B5") (pinfunction "CC2_B5") (pintype "passive"))
      (node (ref "R5") (pin "2") (pinfunction "2_2") (pintype "passive"))
    )
    (net (code "35") (name "Net-(LED1-K)") (class "Default")
      (node (ref "LED1") (pin "1") (pinfunction "K_1") (pintype "passive"))
      (node (ref "R10") (pin "2") (pinfunction "2_2") (pintype "passive"))
    )
    (net (code "36") (name "Net-(LED2-K)") (class "Default")
      (node (ref "LED2") (pin "2") (pinfunction "K_2") (pintype "passive"))
      (node (ref "R12") (pin "2") (pinfunction "2_2") (pintype "passive"))
    )
    (net (code "37") (name "Net-(LED3-C)") (class "Default")
      (node (ref "LED3") (pin "1") (pinfunction "C_1") (pintype "passive"))
      (node (ref "R27") (pin "2") (pinfunction "2_2") (pintype "passive"))
    )
    (net (code "38") (name "Net-(Q1-D-Pad1)") (class "Default")
      (node (ref "Q1") (pin "1") (pinfunction "D_1") (pintype "passive"))
      (node (ref "Q1") (pin "2") (pinfunction "D_2") (pintype "passive"))
      (node (ref "Q1") (pin "5") (pinfunction "D_5") (pintype "passive"))
      (node (ref "Q1") (pin "6") (pinfunction "D_6") (pintype "passive"))
      (node (ref "Q3") (pin "1") (pinfunction "D_1") (pintype "passive"))
      (node (ref "Q3") (pin "2") (pinfunction "D_2") (pintype "passive"))
      (node (ref "Q3") (pin "5") (pinfunction "D_5") (pintype "passive"))
      (node (ref "Q3") (pin "6") (pinfunction "D_6") (pintype "passive"))
    )
    (net (code "39") (name "Net-(Q1-G)") (class "Default")
      (node (ref "Q1") (pin "3") (pinfunction "G_3") (pintype "passive"))
      (node (ref "Q3") (pin "3") (pinfunction "G_3") (pintype "passive"))
      (node (ref "R14") (pin "2") (pinfunction "2_2") (pintype "passive"))
      (node (ref "R15") (pin "2") (pinfunction "2_2") (pintype "passive"))
    )
    (net (code "40") (name "Net-(Q2-D-Pad1)") (class "Default")
      (node (ref "Q2") (pin "1") (pinfunction "D_1") (pintype "passive"))
      (node (ref "Q2") (pin "2") (pinfunction "D_2") (pintype "passive"))
      (node (ref "Q2") (pin "5") (pinfunction "D_5") (pintype "passive"))
      (node (ref "Q2") (pin "6") (pinfunction "D_6") (pintype "passive"))
      (node (ref "Q4") (pin "1") (pinfunction "D_1") (pintype "passive"))
      (node (ref "Q4") (pin "2") (pinfunction "D_2") (pintype "passive"))
      (node (ref "Q4") (pin "5") (pinfunction "D_5") (pintype "passive"))
      (node (ref "Q4") (pin "6") (pinfunction "D_6") (pintype "passive"))
      (node (ref "R14") (pin "1") (pinfunction "1_1") (pintype "passive"))
    )
    (net (code "41") (name "Net-(Q2-G)") (class "Default")
      (node (ref "Q2") (pin "3") (pinfunction "G_3") (pintype "passive"))
      (node (ref "Q4") (pin "3") (pinfunction "G_3") (pintype "passive"))
      (node (ref "R13") (pin "1") (pinfunction "1_1") (pintype "passive"))
      (node (ref "R16") (pin "2") (pinfunction "2_2") (pintype "passive"))
    )
    (net (code "42") (name "Net-(Q5-D)") (class "Default")
      (node (ref "Q5") (pin "3") (pinfunction "D_3") (pintype "passive"))
      (node (ref "R27") (pin "1") (pinfunction "1_1") (pintype "passive"))
    )
    (net (code "43") (name "Net-(Q5-G)") (class "Default")
      (node (ref "Q5") (pin "1") (pinfunction "G_1") (pintype "passive"))
      (node (ref "R28") (pin "1") (pinfunction "1_1") (pintype "passive"))
    )
    (net (code "44") (name "Net-(R18-Pad1)") (class "Default")
      (node (ref "R18") (pin "1") (pinfunction "1_1") (pintype "passive"))
      (node (ref "SW2") (pin "2") (pinfunction "2_2") (pintype "passive"))
    )
    (net (code "45") (name "Net-(R19-Pad2)") (class "Default")
      (node (ref "R19") (pin "2") (pinfunction "2_2") (pintype "passive"))
      (node (ref "SW3") (pin "1") (pinfunction "1_1") (pintype "passive"))
    )
    (net (code "46") (name "Net-(TP16-Test_point)") (class "Default")
      (node (ref "C19") (pin "2") (pinfunction "2_2") (pintype "passive"))
      (node (ref "R22") (pin "1") (pinfunction "1_1") (pintype "passive"))
      (node (ref "R23") (pin "2") (pinfunction "2_2") (pintype "passive"))
      (node (ref "TP16") (pin "TP?") (pinfunction "Test_point_TP?") (pintype "passive"))
      (node (ref "U5") (pin "1") (pinfunction "FB_1") (pintype "passive"))
    )
    (net (code "47") (name "Net-(U2-BTST)") (class "Default")
      (node (ref "C4") (pin "1") (pinfunction "1_1") (pintype "passive"))
      (node (ref "U2") (pin "15") (pinfunction "BTST_15") (pintype "passive"))
    )
    (net (code "48") (name "Net-(U2-ICHG)") (class "Default")
      (node (ref "R1") (pin "2") (pinfunction "2_2") (pintype "passive"))
      (node (ref "U2") (pin "4") (pinfunction "ICHG_4") (pintype "passive"))
    )
    (net (code "49") (name "Net-(U2-TS)") (class "Default")
      (node (ref "R6") (pin "2") (pinfunction "2_2") (pintype "passive"))
      (node (ref "R7") (pin "1") (pinfunction "1_1") (pintype "passive"))
      (node (ref "U2") (pin "7") (pinfunction "TS_7") (pintype "passive"))
    )
    (net (code "50") (name "Net-(U2-VSET)") (class "Default")
      (node (ref "R8") (pin "2") (pinfunction "2_2") (pintype "passive"))
      (node (ref "U2") (pin "9") (pinfunction "VSET_9") (pintype "passive"))
    )
    (net (code "51") (name "Net-(U4-CT)") (class "Default")
      (node (ref "C13") (pin "1") (pinfunction "1_1") (pintype "passive"))
      (node (ref "U4") (pin "6") (pinfunction "CT_6") (pintype "passive"))
    )
    (net (code "52") (name "Net-(U5-SW)") (class "Default")
      (node (ref "L2") (pin "2") (pinfunction "2_2") (pintype "passive"))
      (node (ref "U5") (pin "5") (pinfunction "SW_5") (pintype "passive"))
    )
    (net (code "53") (name "unconnected-(J1-SBU1-PadA8)") (class "Default")
      (node (ref "J1") (pin "A8") (pinfunction "SBU1_A8") (pintype "passive+no_connect"))
    )
    (net (code "54") (name "unconnected-(J1-SBU2-PadB8)") (class "Default")
      (node (ref "J1") (pin "B8") (pinfunction "SBU2_B8") (pintype "passive+no_connect"))
    )
    (net (code "55") (name "unconnected-(J1-SHELL-Pad1)") (class "Default")
      (node (ref "J1") (pin "1") (pinfunction "SHELL_1") (pintype "passive+no_connect"))
    )
    (net (code "56") (name "unconnected-(J1-SHELL-Pad2)") (class "Default")
      (node (ref "J1") (pin "2") (pinfunction "SHELL_2") (pintype "passive+no_connect"))
    )
    (net (code "57") (name "unconnected-(J1-SHELL-Pad3)") (class "Default")
      (node (ref "J1") (pin "3") (pinfunction "SHELL_3") (pintype "passive+no_connect"))
    )
    (net (code "58") (name "unconnected-(J1-SHELL-Pad4)") (class "Default")
      (node (ref "J1") (pin "4") (pinfunction "SHELL_4") (pintype "passive+no_connect"))
    )
    (net (code "59") (name "unconnected-(SW1-Pad1)") (class "Default")
      (node (ref "SW1") (pin "1") (pinfunction "1_1") (pintype "passive+no_connect"))
    )
    (net (code "60") (name "unconnected-(U2-POL-Pad5)") (class "Default")
      (node (ref "U2") (pin "5") (pinfunction "POL_5") (pintype "passive+no_connect"))
    )
  )
)
